# MCU.net
KiCad netlist of a schematic drawn in Altium Designer
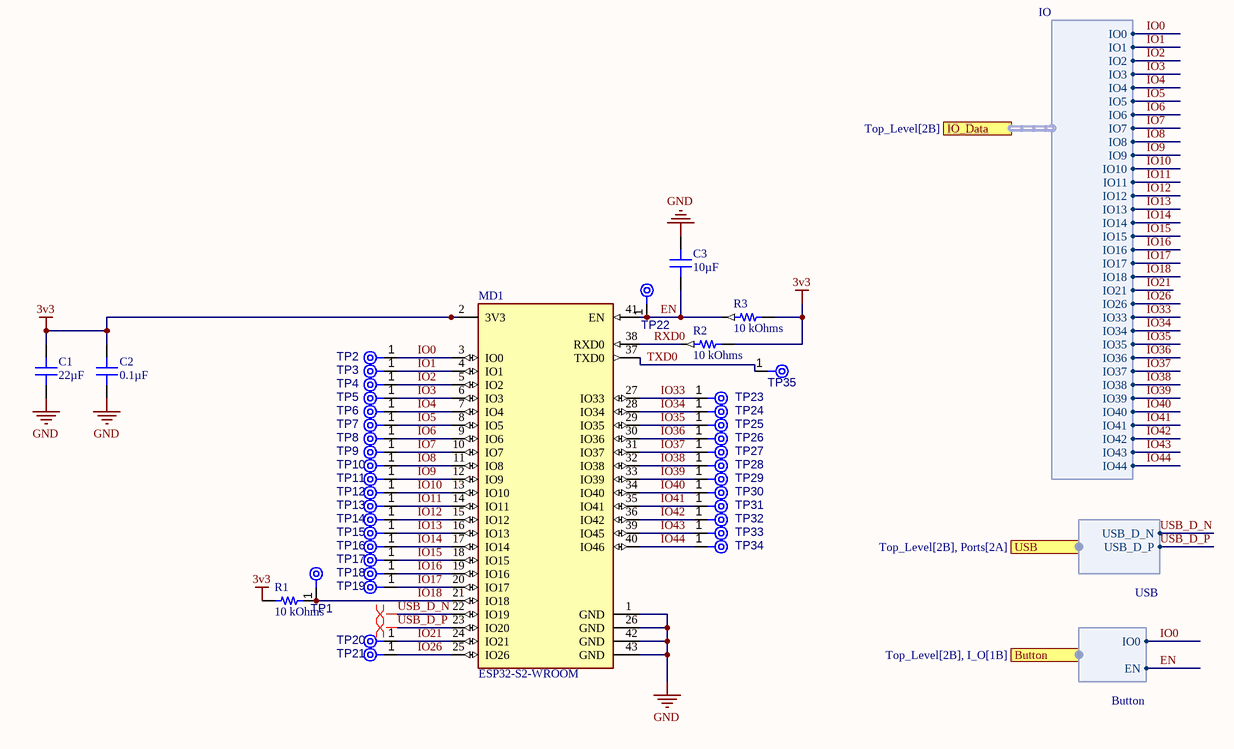
[diagram p0: MCU.SchDoc]

(export (version "E")
  (design (tool "Eeschema 10.0.6"))
  (components
    (comp (ref "C1")
      (value "22µF")
      (footprint "CAP 0805_2012")
      (description "CAP CER 22UF 10V X5R 0805")
      (fields (field (name "PART NUMBER") "0805ZD226MAT2A") (field (name "MANUFACTURER") "AVX Corporation"))
      (libsource (lib "Celestial Altium Library - altium_library") (part "Capacitor"))
    )
    (comp (ref "C2")
      (value "0.1µF")
      (footprint "CAP 0805_2012")
      (description "CAP CER 0.1UF 10V X7R 0805")
      (fields (field (name "PART NUMBER") "0805ZC104KAT2A") (field (name "MANUFACTURER") "AVX Corporation"))
      (libsource (lib "Celestial Altium Library - altium_library") (part "Capacitor"))
    )
    (comp (ref "C3")
      (value "10µF")
      (footprint "CAP 0805_2012")
      (description "CAP CER 10UF 10V X5R 0805")
      (fields (field (name "PART NUMBER") "0805ZD106KAT4A") (field (name "MANUFACTURER") "AVX Corporation"))
      (libsource (lib "Celestial Altium Library - altium_library") (part "Capacitor"))
    )
    (comp (ref "MD1")
      (value "ESP32-S2-WROOM")
      (footprint "FP-ESP32-S2-WROOM-MFG")
      (description "RX TXRX MOD WIFI SURFACE MOUNT")
      (libsource (lib "Altium Content Vault") (part "dfe856f8f0070eb901285bddcc8df6c"))
    )
    (comp (ref "R1")
      (value "10 kOhms")
      (footprint "RES 0805_2012")
      (description "RES 10K OHM 0.5% 1/4W 0805")
      (fields
        (field (name "PART NUMBER") "RK73H2ATTD1002D")
        (field (name "MANUFACTURER") "KOA Speer Electronics, Inc.")
      )
      (libsource (lib "Celestial Altium Library - altium_library") (part "Resistor"))
    )
    (comp (ref "R2")
      (value "10 kOhms")
      (footprint "RES 0805_2012")
      (description "RES 10K OHM 0.5% 1/4W 0805")
      (fields
        (field (name "PART NUMBER") "RK73H2ATTD1002D")
        (field (name "MANUFACTURER") "KOA Speer Electronics, Inc.")
      )
      (libsource (lib "Celestial Altium Library - altium_library") (part "Resistor"))
    )
    (comp (ref "R3")
      (value "10 kOhms")
      (footprint "RES 0805_2012")
      (description "RES 10K OHM 0.5% 1/4W 0805")
      (fields
        (field (name "PART NUMBER") "RK73H2ATTD1002D")
        (field (name "MANUFACTURER") "KOA Speer Electronics, Inc.")
      )
      (libsource (lib "Celestial Altium Library - altium_library") (part "Resistor"))
    )
    (comp (ref "TP1")
      (value "TPAD1.0R")
      (footprint "TP06R")
      (description "1.0mm round testpoint")
      (libsource (lib "Cuvos Pty Ltd") (part "CMP-001-0001-4"))
    )
    (comp (ref "TP2")
      (value "TPAD1.0R")
      (footprint "TP06R")
      (description "1.0mm round testpoint")
      (libsource (lib "Cuvos Pty Ltd") (part "CMP-001-0001-4"))
    )
    (comp (ref "TP3")
      (value "TPAD1.0R")
      (footprint "TP06R")
      (description "1.0mm round testpoint")
      (libsource (lib "Cuvos Pty Ltd") (part "CMP-001-0001-4"))
    )
    (comp (ref "TP4")
      (value "TPAD1.0R")
      (footprint "TP06R")
      (description "1.0mm round testpoint")
      (libsource (lib "Cuvos Pty Ltd") (part "CMP-001-0001-4"))
    )
    (comp (ref "TP5")
      (value "TPAD1.0R")
      (footprint "TP06R")
      (description "1.0mm round testpoint")
      (libsource (lib "Cuvos Pty Ltd") (part "CMP-001-0001-4"))
    )
    (comp (ref "TP6")
      (value "TPAD1.0R")
      (footprint "TP06R")
      (description "1.0mm round testpoint")
      (libsource (lib "Cuvos Pty Ltd") (part "CMP-001-0001-4"))
    )
    (comp (ref "TP7")
      (value "TPAD1.0R")
      (footprint "TP06R")
      (description "1.0mm round testpoint")
      (libsource (lib "Cuvos Pty Ltd") (part "CMP-001-0001-4"))
    )
    (comp (ref "TP8")
      (value "TPAD1.0R")
      (footprint "TP06R")
      (description "1.0mm round testpoint")
      (libsource (lib "Cuvos Pty Ltd") (part "CMP-001-0001-4"))
    )
    (comp (ref "TP9")
      (value "TPAD1.0R")
      (footprint "TP06R")
      (description "1.0mm round testpoint")
      (libsource (lib "Cuvos Pty Ltd") (part "CMP-001-0001-4"))
    )
    (comp (ref "TP10")
      (value "TPAD1.0R")
      (footprint "TP06R")
      (description "1.0mm round testpoint")
      (libsource (lib "Cuvos Pty Ltd") (part "CMP-001-0001-4"))
    )
    (comp (ref "TP11")
      (value "TPAD1.0R")
      (footprint "TP06R")
      (description "1.0mm round testpoint")
      (libsource (lib "Cuvos Pty Ltd") (part "CMP-001-0001-4"))
    )
    (comp (ref "TP12")
      (value "TPAD1.0R")
      (footprint "TP06R")
      (description "1.0mm round testpoint")
      (libsource (lib "Cuvos Pty Ltd") (part "CMP-001-0001-4"))
    )
    (comp (ref "TP13")
      (value "TPAD1.0R")
      (footprint "TP06R")
      (description "1.0mm round testpoint")
      (libsource (lib "Cuvos Pty Ltd") (part "CMP-001-0001-4"))
    )
    (comp (ref "TP14")
      (value "TPAD1.0R")
      (footprint "TP06R")
      (description "1.0mm round testpoint")
      (libsource (lib "Cuvos Pty Ltd") (part "CMP-001-0001-4"))
    )
    (comp (ref "TP15")
      (value "TPAD1.0R")
      (footprint "TP06R")
      (description "1.0mm round testpoint")
      (libsource (lib "Cuvos Pty Ltd") (part "CMP-001-0001-4"))
    )
    (comp (ref "TP16")
      (value "TPAD1.0R")
      (footprint "TP06R")
      (description "1.0mm round testpoint")
      (libsource (lib "Cuvos Pty Ltd") (part "CMP-001-0001-4"))
    )
    (comp (ref "TP17")
      (value "TPAD1.0R")
      (footprint "TP06R")
      (description "1.0mm round testpoint")
      (libsource (lib "Cuvos Pty Ltd") (part "CMP-001-0001-4"))
    )
    (comp (ref "TP18")
      (value "TPAD1.0R")
      (footprint "TP06R")
      (description "1.0mm round testpoint")
      (libsource (lib "Cuvos Pty Ltd") (part "CMP-001-0001-4"))
    )
    (comp (ref "TP19")
      (value "TPAD1.0R")
      (footprint "TP06R")
      (description "1.0mm round testpoint")
      (libsource (lib "Cuvos Pty Ltd") (part "CMP-001-0001-4"))
    )
    (comp (ref "TP20")
      (value "TPAD1.0R")
      (footprint "TP06R")
      (description "1.0mm round testpoint")
      (libsource (lib "Cuvos Pty Ltd") (part "CMP-001-0001-4"))
    )
    (comp (ref "TP21")
      (value "TPAD1.0R")
      (footprint "TP06R")
      (description "1.0mm round testpoint")
      (libsource (lib "Cuvos Pty Ltd") (part "CMP-001-0001-4"))
    )
    (comp (ref "TP22")
      (value "TPAD1.0R")
      (footprint "TP06R")
      (description "1.0mm round testpoint")
      (libsource (lib "Cuvos Pty Ltd") (part "CMP-001-0001-4"))
    )
    (comp (ref "TP23")
      (value "TPAD1.0R")
      (footprint "TP06R")
      (description "1.0mm round testpoint")
      (libsource (lib "Cuvos Pty Ltd") (part "CMP-001-0001-4"))
    )
    (comp (ref "TP24")
      (value "TPAD1.0R")
      (footprint "TP06R")
      (description "1.0mm round testpoint")
      (libsource (lib "Cuvos Pty Ltd") (part "CMP-001-0001-4"))
    )
    (comp (ref "TP25")
      (value "TPAD1.0R")
      (footprint "TP06R")
      (description "1.0mm round testpoint")
      (libsource (lib "Cuvos Pty Ltd") (part "CMP-001-0001-4"))
    )
    (comp (ref "TP26")
      (value "TPAD1.0R")
      (footprint "TP06R")
      (description "1.0mm round testpoint")
      (libsource (lib "Cuvos Pty Ltd") (part "CMP-001-0001-4"))
    )
    (comp (ref "TP27")
      (value "TPAD1.0R")
      (footprint "TP06R")
      (description "1.0mm round testpoint")
      (libsource (lib "Cuvos Pty Ltd") (part "CMP-001-0001-4"))
    )
    (comp (ref "TP28")
      (value "TPAD1.0R")
      (footprint "TP06R")
      (description "1.0mm round testpoint")
      (libsource (lib "Cuvos Pty Ltd") (part "CMP-001-0001-4"))
    )
    (comp (ref "TP29")
      (value "TPAD1.0R")
      (footprint "TP06R")
      (description "1.0mm round testpoint")
      (libsource (lib "Cuvos Pty Ltd") (part "CMP-001-0001-4"))
    )
    (comp (ref "TP30")
      (value "TPAD1.0R")
      (footprint "TP06R")
      (description "1.0mm round testpoint")
      (libsource (lib "Cuvos Pty Ltd") (part "CMP-001-0001-4"))
    )
    (comp (ref "TP31")
      (value "TPAD1.0R")
      (footprint "TP06R")
      (description "1.0mm round testpoint")
      (libsource (lib "Cuvos Pty Ltd") (part "CMP-001-0001-4"))
    )
    (comp (ref "TP32")
      (value "TPAD1.0R")
      (footprint "TP06R")
      (description "1.0mm round testpoint")
      (libsource (lib "Cuvos Pty Ltd") (part "CMP-001-0001-4"))
    )
    (comp (ref "TP33")
      (value "TPAD1.0R")
      (footprint "TP06R")
      (description "1.0mm round testpoint")
      (libsource (lib "Cuvos Pty Ltd") (part "CMP-001-0001-4"))
    )
    (comp (ref "TP34")
      (value "TPAD1.0R")
      (footprint "TP06R")
      (description "1.0mm round testpoint")
      (libsource (lib "Cuvos Pty Ltd") (part "CMP-001-0001-4"))
    )
    (comp (ref "TP35")
      (value "TPAD1.0R")
      (footprint "TP06R")
      (description "1.0mm round testpoint")
      (libsource (lib "Cuvos Pty Ltd") (part "CMP-001-0001-4"))
    )
  )
  (nets
    (net (code "4") (name "/EN") (class "Default")
      (node (ref "C3") (pin "1") (pinfunction "1_1") (pintype "passive"))
      (node (ref "MD1") (pin "41") (pinfunction "EN_41") (pintype "input"))
      (node (ref "R3") (pin "1") (pinfunction "1_1") (pintype "output"))
      (node (ref "TP22") (pin "1") (pinfunction "TP_1") (pintype "passive"))
    )
    (net (code "5") (name "/IO0") (class "Default")
      (node (ref "MD1") (pin "3") (pinfunction "IO0_3") (pintype "bidirectional"))
      (node (ref "TP2") (pin "1") (pinfunction "TP_1") (pintype "passive"))
    )
    (net (code "6") (name "/IO1") (class "Default")
      (node (ref "MD1") (pin "4") (pinfunction "IO1_4") (pintype "bidirectional"))
      (node (ref "TP3") (pin "1") (pinfunction "TP_1") (pintype "passive"))
    )
    (net (code "7") (name "/IO2") (class "Default")
      (node (ref "MD1") (pin "5") (pinfunction "IO2_5") (pintype "bidirectional"))
      (node (ref "TP4") (pin "1") (pinfunction "TP_1") (pintype "passive"))
    )
    (net (code "8") (name "/IO3") (class "Default")
      (node (ref "MD1") (pin "6") (pinfunction "IO3_6") (pintype "bidirectional"))
      (node (ref "TP5") (pin "1") (pinfunction "TP_1") (pintype "passive"))
    )
    (net (code "9") (name "/IO4") (class "Default")
      (node (ref "MD1") (pin "7") (pinfunction "IO4_7") (pintype "bidirectional"))
      (node (ref "TP6") (pin "1") (pinfunction "TP_1") (pintype "passive"))
    )
    (net (code "10") (name "/IO5") (class "Default")
      (node (ref "MD1") (pin "8") (pinfunction "IO5_8") (pintype "bidirectional"))
      (node (ref "TP7") (pin "1") (pinfunction "TP_1") (pintype "passive"))
    )
    (net (code "11") (name "/IO6") (class "Default")
      (node (ref "MD1") (pin "9") (pinfunction "IO6_9") (pintype "bidirectional"))
      (node (ref "TP8") (pin "1") (pinfunction "TP_1") (pintype "passive"))
    )
    (net (code "12") (name "/IO7") (class "Default")
      (node (ref "MD1") (pin "10") (pinfunction "IO7_10") (pintype "bidirectional"))
      (node (ref "TP9") (pin "1") (pinfunction "TP_1") (pintype "passive"))
    )
    (net (code "13") (name "/IO8") (class "Default")
      (node (ref "MD1") (pin "11") (pinfunction "IO8_11") (pintype "bidirectional"))
      (node (ref "TP10") (pin "1") (pinfunction "TP_1") (pintype "passive"))
    )
    (net (code "14") (name "/IO9") (class "Default")
      (node (ref "MD1") (pin "12") (pinfunction "IO9_12") (pintype "bidirectional"))
      (node (ref "TP11") (pin "1") (pinfunction "TP_1") (pintype "passive"))
    )
    (net (code "15") (name "/IO10") (class "Default")
      (node (ref "MD1") (pin "13") (pinfunction "IO10_13") (pintype "bidirectional"))
      (node (ref "TP12") (pin "1") (pinfunction "TP_1") (pintype "passive"))
    )
    (net (code "16") (name "/IO11") (class "Default")
      (node (ref "MD1") (pin "14") (pinfunction "IO11_14") (pintype "bidirectional"))
      (node (ref "TP13") (pin "1") (pinfunction "TP_1") (pintype "passive"))
    )
    (net (code "17") (name "/IO12") (class "Default")
      (node (ref "MD1") (pin "15") (pinfunction "IO12_15") (pintype "bidirectional"))
      (node (ref "TP14") (pin "1") (pinfunction "TP_1") (pintype "passive"))
    )
    (net (code "18") (name "/IO13") (class "Default")
      (node (ref "MD1") (pin "16") (pinfunction "IO13_16") (pintype "bidirectional"))
      (node (ref "TP15") (pin "1") (pinfunction "TP_1") (pintype "passive"))
    )
    (net (code "19") (name "/IO14") (class "Default")
      (node (ref "MD1") (pin "17") (pinfunction "IO14_17") (pintype "bidirectional"))
      (node (ref "TP16") (pin "1") (pinfunction "TP_1") (pintype "passive"))
    )
    (net (code "20") (name "/IO15") (class "Default")
      (node (ref "MD1") (pin "18") (pinfunction "IO15_18") (pintype "bidirectional"))
      (node (ref "TP17") (pin "1") (pinfunction "TP_1") (pintype "passive"))
    )
    (net (code "21") (name "/IO16") (class "Default")
      (node (ref "MD1") (pin "19") (pinfunction "IO16_19") (pintype "bidirectional"))
      (node (ref "TP18") (pin "1") (pinfunction "TP_1") (pintype "passive"))
    )
    (net (code "22") (name "/IO17") (class "Default")
      (node (ref "MD1") (pin "20") (pinfunction "IO17_20") (pintype "bidirectional"))
      (node (ref "TP19") (pin "1") (pinfunction "TP_1") (pintype "passive"))
    )
    (net (code "23") (name "/IO18") (class "Default")
      (node (ref "MD1") (pin "21") (pinfunction "IO18_21") (pintype "bidirectional"))
      (node (ref "R1") (pin "2") (pinfunction "2_2") (pintype "passive"))
      (node (ref "TP1") (pin "1") (pinfunction "TP_1") (pintype "passive"))
    )
    (net (code "24") (name "/IO21") (class "Default")
      (node (ref "MD1") (pin "24") (pinfunction "IO21_24") (pintype "bidirectional"))
      (node (ref "TP20") (pin "1") (pinfunction "TP_1") (pintype "passive"))
    )
    (net (code "25") (name "/IO26") (class "Default")
      (node (ref "MD1") (pin "25") (pinfunction "IO26_25") (pintype "bidirectional"))
      (node (ref "TP21") (pin "1") (pinfunction "TP_1") (pintype "passive"))
    )
    (net (code "26") (name "/IO33") (class "Default")
      (node (ref "MD1") (pin "27") (pinfunction "IO33_27") (pintype "bidirectional"))
      (node (ref "TP23") (pin "1") (pinfunction "TP_1") (pintype "passive"))
    )
    (net (code "27") (name "/IO34") (class "Default")
      (node (ref "MD1") (pin "28") (pinfunction "IO34_28") (pintype "bidirectional"))
      (node (ref "TP24") (pin "1") (pinfunction "TP_1") (pintype "passive"))
    )
    (net (code "28") (name "/IO35") (class "Default")
      (node (ref "MD1") (pin "29") (pinfunction "IO35_29") (pintype "bidirectional"))
      (node (ref "TP25") (pin "1") (pinfunction "TP_1") (pintype "passive"))
    )
    (net (code "29") (name "/IO36") (class "Default")
      (node (ref "MD1") (pin "30") (pinfunction "IO36_30") (pintype "bidirectional"))
      (node (ref "TP26") (pin "1") (pinfunction "TP_1") (pintype "passive"))
    )
    (net (code "30") (name "/IO37") (class "Default")
      (node (ref "MD1") (pin "31") (pinfunction "IO37_31") (pintype "bidirectional"))
      (node (ref "TP27") (pin "1") (pinfunction "TP_1") (pintype "passive"))
    )
    (net (code "31") (name "/IO38") (class "Default")
      (node (ref "MD1") (pin "32") (pinfunction "IO38_32") (pintype "bidirectional"))
      (node (ref "TP28") (pin "1") (pinfunction "TP_1") (pintype "passive"))
    )
    (net (code "32") (name "/IO39") (class "Default")
      (node (ref "MD1") (pin "33") (pinfunction "IO39_33") (pintype "bidirectional"))
      (node (ref "TP29") (pin "1") (pinfunction "TP_1") (pintype "passive"))
    )
    (net (code "33") (name "/IO40") (class "Default")
      (node (ref "MD1") (pin "34") (pinfunction "IO40_34") (pintype "bidirectional"))
      (node (ref "TP30") (pin "1") (pinfunction "TP_1") (pintype "passive"))
    )
    (net (code "34") (name "/IO41") (class "Default")
      (node (ref "MD1") (pin "35") (pinfunction "IO41_35") (pintype "bidirectional"))
      (node (ref "TP31") (pin "1") (pinfunction "TP_1") (pintype "passive"))
    )
    (net (code "35") (name "/IO42") (class "Default")
      (node (ref "MD1") (pin "36") (pinfunction "IO42_36") (pintype "bidirectional"))
      (node (ref "TP32") (pin "1") (pinfunction "TP_1") (pintype "passive"))
    )
    (net (code "36") (name "/IO43") (class "Default")
      (node (ref "MD1") (pin "39") (pinfunction "IO45_39") (pintype "bidirectional"))
      (node (ref "TP33") (pin "1") (pinfunction "TP_1") (pintype "passive"))
    )
    (net (code "37") (name "/IO44") (class "Default")
      (node (ref "MD1") (pin "40") (pinfunction "IO46_40") (pintype "bidirectional"))
      (node (ref "TP34") (pin "1") (pinfunction "TP_1") (pintype "passive"))
    )
    (net (code "38") (name "/RXD0") (class "Default")
      (node (ref "MD1") (pin "38") (pinfunction "RXD0_38") (pintype "input"))
      (node (ref "R2") (pin "1") (pinfunction "1_1") (pintype "output"))
    )
    (net (code "39") (name "/TXD0") (class "Default")
      (node (ref "MD1") (pin "37") (pinfunction "TXD0_37") (pintype "output"))
      (node (ref "TP35") (pin "1") (pinfunction "TP_1") (pintype "passive"))
    )
    (net (code "40") (name "/USB_D_N") (class "Default")
      (node (ref "MD1") (pin "22") (pinfunction "IO19_22") (pintype "bidirectional"))
    )
    (net (code "41") (name "/USB_D_P") (class "Default")
      (node (ref "MD1") (pin "23") (pinfunction "IO20_23") (pintype "bidirectional"))
    )
    (net (code "45") (name "3v3") (class "Default")
      (node (ref "C1") (pin "1") (pinfunction "1_1") (pintype "passive"))
      (node (ref "C2") (pin "1") (pinfunction "1_1") (pintype "passive"))
      (node (ref "MD1") (pin "2") (pinfunction "3V3_2") (pintype "power_in"))
      (node (ref "R1") (pin "1") (pinfunction "1_1") (pintype "output"))
      (node (ref "R2") (pin "2") (pinfunction "2_2") (pintype "passive"))
      (node (ref "R3") (pin "2") (pinfunction "2_2") (pintype "passive"))
    )
    (net (code "46") (name "GND") (class "Default")
      (node (ref "C1") (pin "2") (pinfunction "2_2") (pintype "passive"))
      (node (ref "C2") (pin "2") (pinfunction "2_2") (pintype "passive"))
      (node (ref "C3") (pin "2") (pinfunction "2_2") (pintype "passive"))
      (node (ref "MD1") (pin "1") (pinfunction "GND_1") (pintype "power_in"))
      (node (ref "MD1") (pin "26") (pinfunction "GND_26") (pintype "power_in"))
      (node (ref "MD1") (pin "42") (pinfunction "GND_42") (pintype "power_in"))
      (node (ref "MD1") (pin "43") (pinfunction "GND_43") (pintype "power_in"))
    )
  )
)
